# Alimentacao.net
KiCad netlist of a schematic drawn in Altium Designer
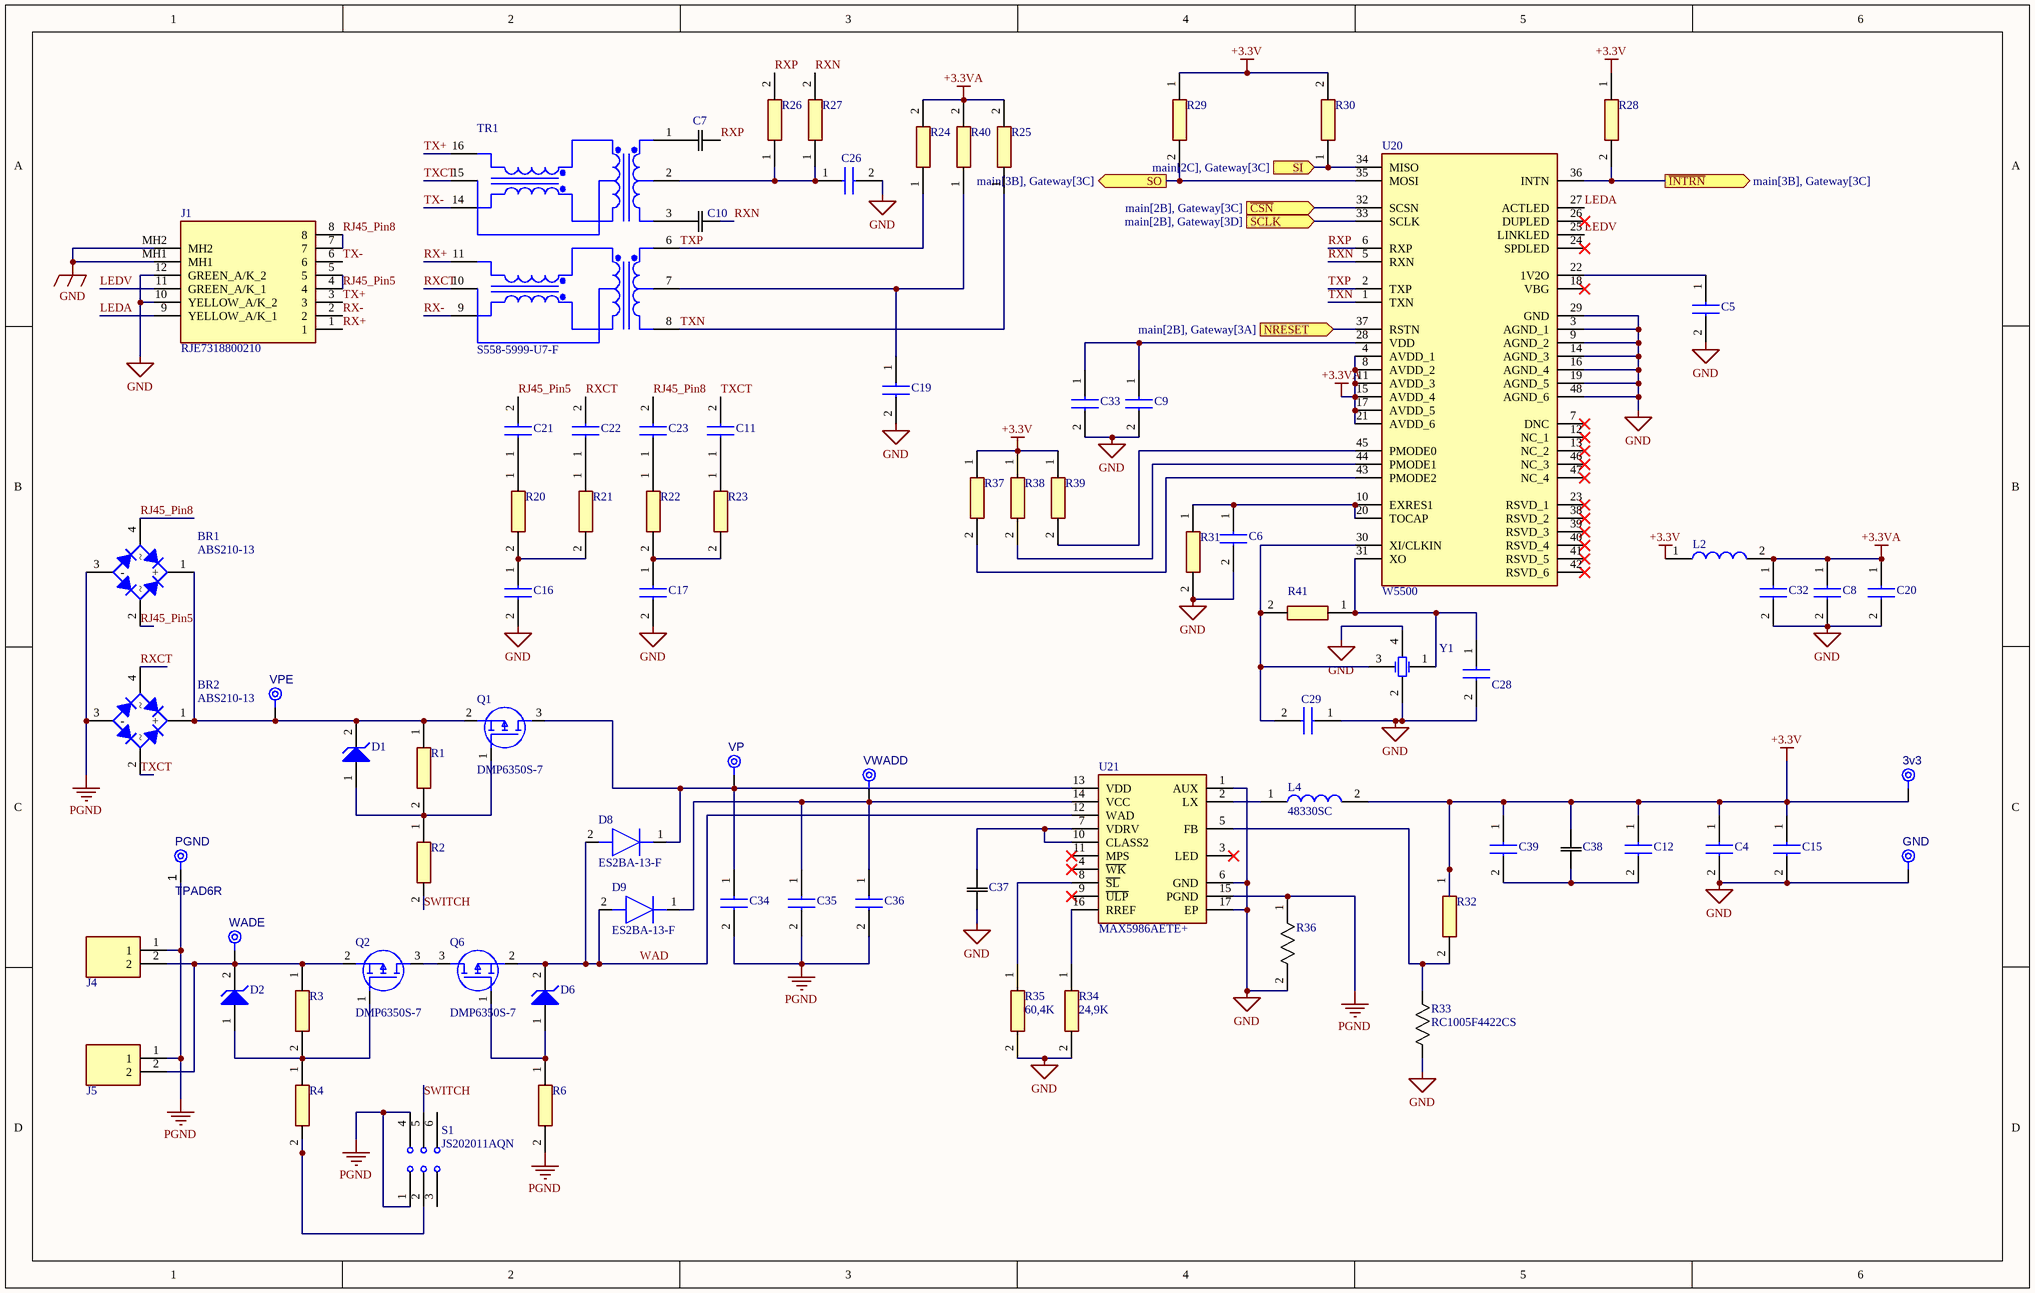
[diagram p0: Alimentacao.SchDoc]

(export (version "E")
  (design (tool "Eeschema 10.0.6"))
  (components
    (comp (ref "3v3")
      (value "TPAD6R")
      (footprint "TP06R")
      (description "0.6mm round")
      (libsource (lib "marina santos") (part "CMP-001-0001-4"))
    )
    (comp (ref "BR1")
      (value "ABS210-13")
      (footprint "SamacSys:ABS21013")
      (description "Bridge Rectifier")
      (fields (field (name "MOUSER PART NUMBER") "621-ABS210-13"))
      (libsource (lib "SamacSys") (part "ABS210-13"))
    )
    (comp (ref "BR2")
      (value "ABS210-13")
      (footprint "SamacSys:ABS21013")
      (description "Bridge Rectifier")
      (fields (field (name "MOUSER PART NUMBER") "621-ABS210-13"))
      (libsource (lib "SamacSys") (part "ABS210-13"))
    )
    (comp (ref "C4")
      (value "C1005X7R1C104KT")
      (footprint "SamacSys:CAPC1005X55N")
      (description "Capacitor")
      (libsource (lib "*") (part "C1005X7R1C104KT"))
    )
    (comp (ref "C5")
      (value "CL05B103KO5NNNC")
      (footprint "SamacSys:CAPC1005X55N")
      (description "Capacitor 10n")
      (libsource (lib "*") (part "CL05B103KO5NNNC"))
    )
    (comp (ref "C6")
      (value "JMK105BC6475MV-F")
      (footprint "SamacSys:CAPC1006X65N")
      (description "Capacitor 4,7u")
      (fields (field (name "MOUSER PART NUMBER") "963-JMK105BC6475MV-F"))
      (libsource (lib "*") (part "JMK105BC6475MV-F"))
    )
    (comp (ref "C7")
      (value "CL05X105KP5NNNC")
      (footprint "CAP_CL05_SAM")
      (description "No Description Available")
      (libsource (lib "CL05X105KP5NNNC") (part "CL05X105KP5NNNC"))
    )
    (comp (ref "C8")
      (value "C1005X7R1C104KT")
      (footprint "SamacSys:CAPC1005X55N")
      (description "Capacitor 100n")
      (libsource (lib "*") (part "C1005X7R1C104KT"))
    )
    (comp (ref "C9")
      (value "C1005X7R1C104KT")
      (footprint "SamacSys:CAPC1005X55N")
      (description "Capacitor 100n")
      (libsource (lib "*") (part "C1005X7R1C104KT"))
    )
    (comp (ref "C10")
      (value "CL05X105KP5NNNC")
      (footprint "CAP_CL05_SAM")
      (description "No Description Available")
      (libsource (lib "CL05X105KP5NNNC") (part "CL05X105KP5NNNC"))
    )
    (comp (ref "C11")
      (value "C1608JB2A223M080AA")
      (footprint "SamacSys:C1608_Commercial")
      (description "Capacitor")
      (fields (field (name "MOUSER PART NUMBER") "810-C1608JB2A223M08A"))
      (libsource (lib "*") (part "C1608JB2A223M080AA"))
    )
    (comp (ref "C12")
      (value "C1005X7R1C104KT")
      (footprint "SamacSys:CAPC1005X55N")
      (description "Capacitor")
      (libsource (lib "*") (part "C1005X7R1C104KT"))
    )
    (comp (ref "C15")
      (value "CL05A106MP8NUB8")
      (footprint "SamacSys:CAPC1005X90N")
      (description "Capacitor 10u")
      (fields (field (name "MOUSER PART NUMBER") "187-CL05A106MP8NUB8"))
      (libsource (lib "*") (part "CL05A106MP8NUB8"))
    )
    (comp (ref "C16")
      (value "CL31B102KJHNNNE")
      (footprint "SamacSys:CAPC3216X180N")
      (description "Capacitor")
      (fields (field (name "MOUSER PART NUMBER") "187-CL31B102KJHNNNE"))
      (libsource (lib "*") (part "CL31B102KJHNNNE"))
    )
    (comp (ref "C17")
      (value "CL31B102KJHNNNE")
      (footprint "SamacSys:CAPC3216X180N")
      (description "Capacitor")
      (fields (field (name "MOUSER PART NUMBER") "187-CL31B102KJHNNNE"))
      (libsource (lib "*") (part "CL31B102KJHNNNE"))
    )
    (comp (ref "C19")
      (value "GRM155R71H223KA12D")
      (footprint "SamacSys:GRM15x")
      (description "Capacitor")
      (fields (field (name "MOUSER PART NUMBER") "81-GRM155R71H223KA12"))
      (libsource (lib "*") (part "GRM155R71H223KA12D"))
    )
    (comp (ref "C20")
      (value "CL05B103KO5NNNC")
      (footprint "SamacSys:CAPC1005X55N")
      (description "Capacitor 10n")
      (libsource (lib "*") (part "CL05B103KO5NNNC"))
    )
    (comp (ref "C21")
      (value "C1608JB2A223M080AA")
      (footprint "SamacSys:C1608_Commercial")
      (description "Capacitor")
      (fields (field (name "MOUSER PART NUMBER") "810-C1608JB2A223M08A"))
      (libsource (lib "*") (part "C1608JB2A223M080AA"))
    )
    (comp (ref "C22")
      (value "C1608JB2A223M080AA")
      (footprint "SamacSys:C1608_Commercial")
      (description "Capacitor")
      (fields (field (name "MOUSER PART NUMBER") "810-C1608JB2A223M08A"))
      (libsource (lib "*") (part "C1608JB2A223M080AA"))
    )
    (comp (ref "C23")
      (value "C1608JB2A223M080AA")
      (footprint "SamacSys:C1608_Commercial")
      (description "Capacitor")
      (fields (field (name "MOUSER PART NUMBER") "810-C1608JB2A223M08A"))
      (libsource (lib "*") (part "C1608JB2A223M080AA"))
    )
    (comp (ref "C26")
      (value "C1005X5R1E104K050BC")
      (footprint "SamacSys:CAPC1005X55N")
      (description "Capacitor")
      (fields (field (name "MOUSER PART NUMBER") "810-C1005X5R1E104K"))
      (libsource (lib "*") (part "C1005X5R1E104K050BC"))
    )
    (comp (ref "C28")
      (value "C1005C0G1H150JT")
      (footprint "SamacSys:CAPC1005X55N")
      (description "Capacitor 15pF")
      (fields (field (name "MANUFACTURER_PART_NUMBER") "CC0402JRNPO9BN150"))
      (libsource (lib "*") (part "CC0402JRNPO9BN150"))
    )
    (comp (ref "C29")
      (value "C1005C0G1H150JT")
      (footprint "SamacSys:CAPC1005X55N")
      (description "Capacitor 15pF")
      (fields (field (name "MANUFACTURER_PART_NUMBER") "CC0402JRNPO9BN150"))
      (libsource (lib "*") (part "CC0402JRNPO9BN150"))
    )
    (comp (ref "C32")
      (value "JMK105BC6475MV-F")
      (footprint "SamacSys:CAPC1006X65N")
      (description "Capacitor 4,7u")
      (fields (field (name "MOUSER PART NUMBER") "963-JMK105BC6475MV-F"))
      (libsource (lib "*") (part "JMK105BC6475MV-F"))
    )
    (comp (ref "C33")
      (value "JMK105BC6475MV-F")
      (footprint "SamacSys:CAPC1006X65N")
      (description "Capacitor 4,7u")
      (fields (field (name "MOUSER PART NUMBER") "963-JMK105BC6475MV-F"))
      (libsource (lib "*") (part "JMK105BC6475MV-F"))
    )
    (comp (ref "C34")
      (value "CC0805KKX7R0BB683")
      (footprint "SamacSys:CAPC2012X145N")
      (description "Capacitor 0,068u")
      (fields (field (name "MOUSER PART NUMBER") "603-CC0805KR0BB683"))
      (libsource (lib "*") (part "CC0805KKX7R0BB683"))
    )
    (comp (ref "C35")
      (value "CL21Y105KCYVPNE")
      (footprint "SamacSys:CAPC2012X145N")
      (description "Capacitor")
      (libsource (lib "SamacSys") (part "CL21Y105KCYVPNE"))
    )
    (comp (ref "C36")
      (value "GRM32ER71J106KA12L")
      (footprint "SamacSys:CAPC3225X270N")
      (description "Capacitor 10u")
      (fields (field (name "MOUSER PART NUMBER") "81-GRM32ER71J106KA2L"))
      (libsource (lib "*") (part "GRM32ER71J106KA12L"))
    )
    (comp (ref "C37")
      (value "CL05X105KP5NNNC")
      (footprint "CAP_CL_05_SAM")
      (description "1u")
      (libsource (lib "CL05X105KP5NNNC") (part "CL05X105KP5NNNC"))
    )
    (comp (ref "C38")
      (value "CL05X105KP5NNNC")
      (footprint "CAP_CL_05_SAM")
      (description "No Description Available")
      (libsource (lib "CL05X105KP5NNNC") (part "CL05X105KP5NNNC"))
    )
    (comp (ref "C39")
      (value "GRM21BR61A476ME15L")
      (footprint "SamacSys:CAPC2012X145N")
      (description "Capacitor")
      (fields (field (name "MOUSER PART NUMBER") "81-GRM21BR61A476ME5L"))
      (libsource (lib "*") (part "GRM21BR61A476ME15L"))
    )
    (comp (ref "D1")
      (value "MMSZ5240B-7-F")
      (footprint "SamacSys:SOD3716X145N")
      (description "D2")
      (fields (field (name "MOUSER PART NUMBER") "621-MMSZ5240B-F"))
      (libsource (lib "SamacSys") (part "MMSZ5240B-7-F"))
    )
    (comp (ref "D2")
      (value "MMSZ5240B-7-F")
      (footprint "SamacSys:SOD3716X145N")
      (description "D2")
      (fields (field (name "MOUSER PART NUMBER") "621-MMSZ5240B-F"))
      (libsource (lib "SamacSys") (part "MMSZ5240B-7-F"))
    )
    (comp (ref "D6")
      (value "MMSZ5240B-7-F")
      (footprint "SamacSys:SOD3716X145N")
      (description "D2")
      (fields (field (name "MOUSER PART NUMBER") "621-MMSZ5240B-F"))
      (libsource (lib "SamacSys") (part "MMSZ5240B-7-F"))
    )
    (comp (ref "D8")
      (value "ES2BA-13-F")
      (footprint "SamacSys:DIOM5226X230N")
      (description "Diode")
      (fields (field (name "MOUSER PART NUMBER") "621-ES2BA-F"))
      (libsource (lib "*") (part "ES2BA-13-F"))
    )
    (comp (ref "D9")
      (value "ES2BA-13-F")
      (footprint "SamacSys:DIOM5226X230N")
      (description "Diode")
      (fields (field (name "MOUSER PART NUMBER") "621-ES2BA-F"))
      (libsource (lib "*") (part "ES2BA-13-F"))
    )
    (comp (ref "GND")
      (value "TPAD6R")
      (footprint "TP06R")
      (description "0.6mm round")
      (libsource (lib "marina santos") (part "CMP-001-0001-4"))
    )
    (comp (ref "J1")
      (value "RJE7318800210")
      (footprint "SamacSys:RJE7318800210")
      (description "Connector")
      (fields (field (name "MOUSER PART NUMBER") "523-RJE7318800210"))
      (libsource (lib "SamacSys") (part "RJE7318800210"))
    )
    (comp (ref "J4")
      (value "OQ0232510000G")
      (footprint "SamacSys:OQ0232510000G")
      (description "Connector")
      (fields (field (name "MOUSER PART NUMBER") "649-220110-D021A01LF"))
      (libsource (lib "*") (part "OQ0232510000G"))
    )
    (comp (ref "J5")
      (value "OQ0232510000G")
      (footprint "SamacSys:OQ0232510000G")
      (description "Connector")
      (fields (field (name "MOUSER PART NUMBER") "649-220110-D021A01LF"))
      (libsource (lib "*") (part "OQ0232510000G"))
    )
    (comp (ref "L2")
      (value "FBMH1608HM101-T")
      (footprint "SamacSys:INDC1608X90N")
      (description "Ferrite Bead")
      (fields (field (name "MOUSER PART NUMBER") "963-FBMH1608HM101-T"))
      (libsource (lib "SamacSys") (part "FBMH1608HM101-T"))
    )
    (comp (ref "L4")
      (value "48330SC")
      (footprint "SamacSys:48101SC")
      (description "Inductor")
      (fields
        (field (name "MANUFACTURER_PART_NUMBER") "48101SC")
        (field (name "MOUSER PART NUMBER") "580-48101SC")
      )
      (libsource (lib "SamacSys") (part "48101SC"))
    )
    (comp (ref "PGND")
      (value "TPAD6R")
      (footprint "TP06R")
      (description "0.6mm round")
      (libsource (lib "") (part "CMP-001-0001-4_1"))
    )
    (comp (ref "Q1")
      (value "DMP6350S-7")
      (footprint "SamacSys:SOT96P240X110-3N")
      (description "MOSFET (P-Channel)")
      (fields (field (name "MOUSER PART NUMBER") "621-DMP6350S-7"))
      (libsource (lib "*") (part "DMP6350S-7"))
    )
    (comp (ref "Q2")
      (value "DMP6350S-7")
      (footprint "SamacSys:SOT96P240X110-3N")
      (description "MOSFET (P-Channel)")
      (fields (field (name "MOUSER PART NUMBER") "621-DMP6350S-7"))
      (libsource (lib "*") (part "DMP6350S-7"))
    )
    (comp (ref "Q6")
      (value "DMP6350S-7")
      (footprint "SamacSys:SOT96P240X110-3N")
      (description "MOSFET (P-Channel)")
      (fields (field (name "MOUSER PART NUMBER") "621-DMP6350S-7"))
      (libsource (lib "*") (part "DMP6350S-7"))
    )
    (comp (ref "R1")
      (value "R0402_1%_100_K__RC0402FR-07100KL_")
      (footprint "SamacSys:RESC1005X40N")
      (description "Resistor 100k")
      (fields (field (name "MANUFACTURER_PART_NUMBER") "R0402 1% 100 K (RC0402FR-07100KL)"))
      (libsource (lib "*") (part "R0402_1%_100_K__RC0402FR-07100KL_"))
    )
    (comp (ref "R2")
      (value "R0402_1%_100_K__RC0402FR-07100KL_")
      (footprint "SamacSys:RESC1005X40N")
      (description "Resistor 100k")
      (fields (field (name "MANUFACTURER_PART_NUMBER") "R0402 1% 100 K (RC0402FR-07100KL)"))
      (libsource (lib "*") (part "R0402_1%_100_K__RC0402FR-07100KL_"))
    )
    (comp (ref "R3")
      (value "R0402_1%_100_K__RC0402FR-07100KL_")
      (footprint "SamacSys:RESC1005X40N")
      (description "Resistor 100k")
      (fields (field (name "MANUFACTURER_PART_NUMBER") "R0402 1% 100 K (RC0402FR-07100KL)"))
      (libsource (lib "*") (part "R0402_1%_100_K__RC0402FR-07100KL_"))
    )
    (comp (ref "R4")
      (value "R0402_1%_100_K__RC0402FR-07100KL_")
      (footprint "SamacSys:RESC1005X40N")
      (description "Resistor 100k")
      (fields (field (name "MANUFACTURER_PART_NUMBER") "R0402 1% 100 K (RC0402FR-07100KL)"))
      (libsource (lib "*") (part "R0402_1%_100_K__RC0402FR-07100KL_"))
    )
    (comp (ref "R6")
      (value "R0402_1%_100_K__RC0402FR-07100KL_")
      (footprint "SamacSys:RESC1005X40N")
      (description "Resistor 100k")
      (fields (field (name "MANUFACTURER_PART_NUMBER") "R0402 1% 100 K (RC0402FR-07100KL)"))
      (libsource (lib "*") (part "R0402_1%_100_K__RC0402FR-07100KL_"))
    )
    (comp (ref "R20")
      (value "RC0603FR-0775RL")
      (footprint "SamacSys:RESC1608X55N")
      (description "Resistor")
      (fields (field (name "MOUSER PART NUMBER") "603-RC0603FR-0775RL"))
      (libsource (lib "*") (part "RC0603FR-0775RL"))
    )
    (comp (ref "R21")
      (value "RC0603FR-0775RL")
      (footprint "SamacSys:RESC1608X55N")
      (description "Resistor")
      (fields (field (name "MOUSER PART NUMBER") "603-RC0603FR-0775RL"))
      (libsource (lib "*") (part "RC0603FR-0775RL"))
    )
    (comp (ref "R22")
      (value "RC0603FR-0775RL")
      (footprint "SamacSys:RESC1608X55N")
      (description "Resistor")
      (fields (field (name "MOUSER PART NUMBER") "603-RC0603FR-0775RL"))
      (libsource (lib "*") (part "RC0603FR-0775RL"))
    )
    (comp (ref "R23")
      (value "RC0603FR-0775RL")
      (footprint "SamacSys:RESC1608X55N")
      (description "Resistor")
      (fields (field (name "MOUSER PART NUMBER") "603-RC0603FR-0775RL"))
      (libsource (lib "*") (part "RC0603FR-0775RL"))
    )
    (comp (ref "R24")
      (value "RC0402FR-0749R9L")
      (footprint "SamacSys:RESC1005X40N")
      (description "Resistor 49,9 ohms")
      (fields (field (name "MOUSER PART NUMBER") "603-RC0402FR-0749R9L"))
      (libsource (lib "*") (part "RC0402FR-0749R9L"))
    )
    (comp (ref "R25")
      (value "RC0402FR-0749R9L")
      (footprint "SamacSys:RESC1005X40N")
      (description "Resistor 49,9 ohms")
      (fields (field (name "MOUSER PART NUMBER") "603-RC0402FR-0749R9L"))
      (libsource (lib "*") (part "RC0402FR-0749R9L"))
    )
    (comp (ref "R26")
      (value "RC0402FR-0782RL")
      (footprint "SamacSys:RESC1005X40N")
      (description "Resistor")
      (fields (field (name "MOUSER PART NUMBER") "603-RC0402FR-0782RL"))
      (libsource (lib "*") (part "RC0402FR-0782RL"))
    )
    (comp (ref "R27")
      (value "RC0402FR-0782RL")
      (footprint "SamacSys:RESC1005X40N")
      (description "Resistor")
      (fields (field (name "MOUSER PART NUMBER") "603-RC0402FR-0782RL"))
      (libsource (lib "*") (part "RC0402FR-0782RL"))
    )
    (comp (ref "R28")
      (value "RC0402FR-074K7L")
      (footprint "SamacSys:RESC1005X40N")
      (description "Resistor 4,7K")
      (fields (field (name "MOUSER PART NUMBER") "603-RC0402FR-074K7L"))
      (libsource (lib "*") (part "RC0402FR-074K7L"))
    )
    (comp (ref "R29")
      (value "RC0402FR-074K7L")
      (footprint "SamacSys:RESC1005X40N")
      (description "Resistor 4,7K")
      (fields (field (name "MOUSER PART NUMBER") "603-RC0402FR-074K7L"))
      (libsource (lib "*") (part "RC0402FR-074K7L"))
    )
    (comp (ref "R30")
      (value "RC0402FR-074K7L")
      (footprint "SamacSys:RESC1005X40N")
      (description "Resistor 4,7 K")
      (fields (field (name "MOUSER PART NUMBER") "603-RC0402FR-074K7L"))
      (libsource (lib "") (part "RC0402FR-074K7L_1"))
    )
    (comp (ref "R31")
      (value "RC0402FR-0712K4L")
      (footprint "SamacSys:RESC1005X40N")
      (description "Resistor 12,4K")
      (fields (field (name "MOUSER PART NUMBER") "603-RC0402FR-0712K4L"))
      (libsource (lib "*") (part "RC0402FR-0712K4L"))
    )
    (comp (ref "R32")
      (value "RC0402FR-0775KL")
      (footprint "SamacSys:RESC1005X40N")
      (description "Resistor")
      (fields (field (name "MOUSER PART NUMBER") "603-RC0402FR-0775KL"))
      (libsource (lib "*") (part "RC0402FR-0775KL"))
    )
    (comp (ref "R33")
      (value "RC1005F4422CS")
      (footprint "RES_1005_SAM-M")
      (description "No Description Available")
      (libsource (lib "RC1005F4422CS") (part "RC1005F4422CS"))
    )
    (comp (ref "R34")
      (value "24,9K")
      (footprint "SamacSys:RESC1005X40N")
      (description "Resistor")
      (fields
        (field (name "MANUFACTURER_PART_NUMBER") "RC0402FR-0724K9L")
        (field (name "MOUSER PART NUMBER") "603-RC0402FR-0724K9L")
      )
      (libsource (lib "*") (part "RC0402FR-0724K9L"))
    )
    (comp (ref "R35")
      (value "60,4K")
      (footprint "SamacSys:RESC1005X40N")
      (description "Resistor 60,4K")
      (fields
        (field (name "MANUFACTURER_PART_NUMBER") "RC0402FR-0760K4L")
        (field (name "MOUSER PART NUMBER") "603-RC0402FR-0760K4L")
      )
      (libsource (lib "*") (part "RC0402FR-0760K4L"))
    )
    (comp (ref "R36")
      (value "RC0805JR-070RL")
      (footprint "SamacSys:CAPC2012X60N")
      (description "Capacitor 0 ohms")
      (fields (field (name "MOUSER PART NUMBER") "603-RC0805JR-070RL"))
      (libsource (lib "SamacSys") (part "RC0805JR-070RL"))
    )
    (comp (ref "R37")
      (value "RC0402FR-0710KL")
      (footprint "SamacSys:RESC1005X40N")
      (description "Resistor 10K")
      (fields (field (name "MOUSER PART NUMBER") "603-RC0402FR-0710KL"))
      (libsource (lib "*") (part "RC0402FR-0710KL"))
    )
    (comp (ref "R38")
      (value "RC0402FR-0710KL")
      (footprint "SamacSys:RESC1005X40N")
      (description "Resistor 10K")
      (fields (field (name "MOUSER PART NUMBER") "603-RC0402FR-0710KL"))
      (libsource (lib "*") (part "RC0402FR-0710KL"))
    )
    (comp (ref "R39")
      (value "RC0402FR-0710KL")
      (footprint "SamacSys:RESC1005X40N")
      (description "Resistor 10K")
      (fields (field (name "MOUSER PART NUMBER") "603-RC0402FR-0710KL"))
      (libsource (lib "*") (part "RC0402FR-0710KL"))
    )
    (comp (ref "R40")
      (value "RC0402FR-0710RL")
      (footprint "SamacSys:RESC1005X40N")
      (description "Resistor 10 ohms")
      (fields (field (name "MOUSER PART NUMBER") "603-RC0402FR-0710RL"))
      (libsource (lib "*") (part "RC0402FR-0710RL"))
    )
    (comp (ref "R41")
      (value "RC0402FR-071ML")
      (footprint "SamacSys:RESC1005X40N")
      (description "Resistor 1M")
      (fields (field (name "MOUSER PART NUMBER") "603-RC0402FR-071ML"))
      (libsource (lib "*") (part "RC0402FR-071ML"))
    )
    (comp (ref "S1")
      (value "JS202011AQN")
      (footprint "SamacSys:JS202011AQN")
      (description "Switch")
      (fields (field (name "MOUSER PART NUMBER") "611-JS202011AQN"))
      (libsource (lib "SamacSys") (part "JS202011AQN"))
    )
    (comp (ref "TR1")
      (value "S558-5999-U7-F")
      (footprint "SamacSys:SOIC127P920X571-16N")
      (description "Integrated Circuit")
      (fields (field (name "MOUSER PART NUMBER") "530-S558-5999-U7-F"))
      (libsource (lib "SamacSys") (part "S558-5999-U7-F"))
    )
    (comp (ref "U20")
      (value "W5500")
      (footprint "SamacSys:QFP50P900X900X160-48N")
      (description "Integrated Circuit")
      (fields (field (name "MOUSER PART NUMBER") "950-W5500"))
      (libsource (lib "SamacSys") (part "W5500"))
    )
    (comp (ref "U21")
      (value "MAX5986AETE+")
      (footprint "SamacSys:QFN80P500X500X80-17N")
      (description "Integrated Circuit")
      (fields (field (name "MOUSER PART NUMBER") "700-MAX5986AETE+"))
      (libsource (lib "SamacSys") (part "MAX5986AETE+"))
    )
    (comp (ref "VP")
      (value "TPAD6R")
      (footprint "TP06R")
      (description "0.6mm round")
      (libsource (lib "marina santos") (part "CMP-001-0001-4"))
    )
    (comp (ref "VPE")
      (value "TPAD6R")
      (footprint "TP06R")
      (description "0.6mm round")
      (libsource (lib "marina santos") (part "CMP-001-0001-4"))
    )
    (comp (ref "VWADD")
      (value "TPAD6R")
      (footprint "TP06R")
      (description "0.6mm round")
      (libsource (lib "marina santos") (part "CMP-001-0001-4"))
    )
    (comp (ref "WADE")
      (value "TPAD6R")
      (footprint "TP06R")
      (description "0.6mm round")
      (libsource (lib "marina santos") (part "CMP-001-0001-4"))
    )
    (comp (ref "Y1")
      (value "RH100-25.000-12-F-1010-TR")
      (footprint "SamacSys:RH1002500012F1010TR")
      (description "Crystal or Oscillator")
      (libsource (lib "SamacSys") (part "RH100-25.000-12-F-1010-TR"))
    )
  )
  (nets
    (net (code "1") (name "+3.3V") (class "Default")
      (node (ref "3v3") (pin "1") (pinfunction "TP_1") (pintype "passive"))
      (node (ref "C12") (pin "1") (pinfunction "1_1") (pintype "passive"))
      (node (ref "C15") (pin "1") (pinfunction "1_1") (pintype "passive"))
      (node (ref "C38") (pin "2") (pinfunction "2_2") (pintype "passive"))
      (node (ref "C39") (pin "1") (pinfunction "1_1") (pintype "passive"))
      (node (ref "C4") (pin "1") (pinfunction "1_1") (pintype "passive"))
      (node (ref "L2") (pin "1") (pinfunction "1_1") (pintype "passive"))
      (node (ref "L4") (pin "2") (pinfunction "2_2") (pintype "passive"))
      (node (ref "R28") (pin "1") (pinfunction "1_1") (pintype "passive"))
      (node (ref "R29") (pin "1") (pinfunction "1_1") (pintype "passive"))
      (node (ref "R30") (pin "2") (pinfunction "2_2") (pintype "passive"))
      (node (ref "R32") (pin "1") (pinfunction "1_1") (pintype "passive"))
      (node (ref "R37") (pin "1") (pinfunction "1_1") (pintype "passive"))
      (node (ref "R38") (pin "1") (pinfunction "1_1") (pintype "passive"))
      (node (ref "R39") (pin "1") (pinfunction "1_1") (pintype "passive"))
    )
    (net (code "2") (name "+3.3VA") (class "Default")
      (node (ref "C20") (pin "1") (pinfunction "1_1") (pintype "passive"))
      (node (ref "C32") (pin "1") (pinfunction "1_1") (pintype "passive"))
      (node (ref "C8") (pin "1") (pinfunction "1_1") (pintype "passive"))
      (node (ref "L2") (pin "2") (pinfunction "2_2") (pintype "passive"))
      (node (ref "R24") (pin "2") (pinfunction "2_2") (pintype "passive"))
      (node (ref "R25") (pin "2") (pinfunction "2_2") (pintype "passive"))
      (node (ref "R40") (pin "2") (pinfunction "2_2") (pintype "passive"))
      (node (ref "U20") (pin "11") (pinfunction "AVDD_3_11") (pintype "passive"))
      (node (ref "U20") (pin "15") (pinfunction "AVDD_4_15") (pintype "passive"))
      (node (ref "U20") (pin "17") (pinfunction "AVDD_5_17") (pintype "passive"))
      (node (ref "U20") (pin "21") (pinfunction "AVDD_6_21") (pintype "passive"))
      (node (ref "U20") (pin "4") (pinfunction "AVDD_1_4") (pintype "passive"))
      (node (ref "U20") (pin "8") (pinfunction "AVDD_2_8") (pintype "passive"))
    )
    (net (code "3") (name "/LEDA") (class "Default")
      (node (ref "J1") (pin "9") (pinfunction "YELLOW_A/K_1_9") (pintype "passive"))
      (node (ref "U20") (pin "27") (pinfunction "ACTLED_27") (pintype "passive"))
    )
    (net (code "4") (name "/LEDV") (class "Default")
      (node (ref "J1") (pin "11") (pinfunction "GREEN_A/K_1_11") (pintype "passive"))
      (node (ref "U20") (pin "25") (pinfunction "LINKLED_25") (pintype "passive"))
    )
    (net (code "5") (name "/NRESET") (class "Default")
      (node (ref "U20") (pin "37") (pinfunction "RSTN_37") (pintype "passive"))
    )
    (net (code "6") (name "/RJ45_Pin5") (class "Default")
      (node (ref "BR1") (pin "2") (pinfunction "~_2") (pintype "passive"))
      (node (ref "C21") (pin "2") (pinfunction "2_2") (pintype "passive"))
      (node (ref "J1") (pin "4") (pinfunction "4_4") (pintype "passive"))
      (node (ref "J1") (pin "5") (pinfunction "5_5") (pintype "passive"))
    )
    (net (code "7") (name "/RJ45_Pin8") (class "Default")
      (node (ref "BR1") (pin "4") (pinfunction "~_4") (pintype "passive"))
      (node (ref "C23") (pin "2") (pinfunction "2_2") (pintype "passive"))
      (node (ref "J1") (pin "7") (pinfunction "7_7") (pintype "passive"))
      (node (ref "J1") (pin "8") (pinfunction "8_8") (pintype "passive"))
    )
    (net (code "8") (name "/RX+") (class "Default")
      (node (ref "J1") (pin "1") (pinfunction "1_1") (pintype "passive"))
      (node (ref "TR1") (pin "11") (pinfunction "RX+_11") (pintype "passive"))
    )
    (net (code "9") (name "/RX-") (class "Default")
      (node (ref "J1") (pin "2") (pinfunction "2_2") (pintype "passive"))
      (node (ref "TR1") (pin "9") (pinfunction "RX-_9") (pintype "passive"))
    )
    (net (code "10") (name "/RXCT") (class "Default")
      (node (ref "BR2") (pin "4") (pinfunction "~_4") (pintype "passive"))
      (node (ref "C22") (pin "2") (pinfunction "2_2") (pintype "passive"))
      (node (ref "TR1") (pin "10") (pinfunction "RXCT_10") (pintype "passive"))
    )
    (net (code "11") (name "/RXN") (class "Default")
      (node (ref "C10") (pin "2") (pinfunction "2_2") (pintype "passive"))
      (node (ref "R27") (pin "2") (pinfunction "2_2") (pintype "passive"))
      (node (ref "U20") (pin "5") (pinfunction "RXN_5") (pintype "passive"))
    )
    (net (code "12") (name "/RXP") (class "Default")
      (node (ref "C7") (pin "2") (pinfunction "2_2") (pintype "passive"))
      (node (ref "R26") (pin "2") (pinfunction "2_2") (pintype "passive"))
      (node (ref "U20") (pin "6") (pinfunction "RXP_6") (pintype "passive"))
    )
    (net (code "13") (name "/SCLK") (class "Default")
      (node (ref "U20") (pin "33") (pinfunction "SCLK_33") (pintype "passive"))
    )
    (net (code "14") (name "/SI") (class "Default")
      (node (ref "R30") (pin "1") (pinfunction "1_1") (pintype "passive"))
      (node (ref "U20") (pin "34") (pinfunction "MISO_34") (pintype "passive"))
    )
    (net (code "15") (name "/SO") (class "Default")
      (node (ref "R29") (pin "2") (pinfunction "2_2") (pintype "passive"))
      (node (ref "U20") (pin "35") (pinfunction "MOSI_35") (pintype "passive"))
    )
    (net (code "16") (name "/SWITCH") (class "Default")
      (node (ref "R2") (pin "2") (pinfunction "2_2") (pintype "passive"))
      (node (ref "S1") (pin "5") (pinfunction "C_2_5") (pintype "passive"))
    )
    (net (code "17") (name "/TX+") (class "Default")
      (node (ref "J1") (pin "3") (pinfunction "3_3") (pintype "passive"))
      (node (ref "TR1") (pin "16") (pinfunction "TX+_16") (pintype "passive"))
    )
    (net (code "18") (name "/TX-") (class "Default")
      (node (ref "J1") (pin "6") (pinfunction "6_6") (pintype "passive"))
      (node (ref "TR1") (pin "14") (pinfunction "TX-_14") (pintype "passive"))
    )
    (net (code "19") (name "/TXCT") (class "Default")
      (node (ref "BR2") (pin "2") (pinfunction "~_2") (pintype "passive"))
      (node (ref "C11") (pin "2") (pinfunction "2_2") (pintype "passive"))
      (node (ref "TR1") (pin "15") (pinfunction "TXCT_15") (pintype "passive"))
    )
    (net (code "20") (name "/TXN") (class "Default")
      (node (ref "R25") (pin "1") (pinfunction "1_1") (pintype "passive"))
      (node (ref "TR1") (pin "8") (pinfunction "RD-_8") (pintype "passive"))
      (node (ref "U20") (pin "1") (pinfunction "TXN_1") (pintype "passive"))
    )
    (net (code "21") (name "/TXP") (class "Default")
      (node (ref "R24") (pin "1") (pinfunction "1_1") (pintype "passive"))
      (node (ref "TR1") (pin "6") (pinfunction "RD+_6") (pintype "passive"))
      (node (ref "U20") (pin "2") (pinfunction "TXP_2") (pintype "passive"))
    )
    (net (code "22") (name "/WAD") (class "Default")
      (node (ref "D6") (pin "2") (pinfunction "A_2") (pintype "passive"))
      (node (ref "D8") (pin "2") (pinfunction "A_2") (pintype "passive"))
      (node (ref "D9") (pin "2") (pinfunction "A_2") (pintype "passive"))
      (node (ref "Q6") (pin "2") (pinfunction "S_2") (pintype "passive"))
      (node (ref "U21") (pin "12") (pinfunction "WAD_12") (pintype "passive"))
    )
    (net (code "23") (name "/~{CSN}") (class "Default")
      (node (ref "U20") (pin "32") (pinfunction "SCSN_32") (pintype "passive"))
    )
    (net (code "24") (name "/~{INTRN}") (class "Default")
      (node (ref "R28") (pin "2") (pinfunction "2_2") (pintype "passive"))
      (node (ref "U20") (pin "36") (pinfunction "INTN_36") (pintype "passive"))
    )
    (net (code "25") (name "GND") (class "Default")
      (node (ref "C15") (pin "2") (pinfunction "2_2") (pintype "passive"))
      (node (ref "C16") (pin "2") (pinfunction "2_2") (pintype "passive"))
      (node (ref "C17") (pin "2") (pinfunction "2_2") (pintype "passive"))
      (node (ref "C19") (pin "2") (pinfunction "2_2") (pintype "passive"))
      (node (ref "C20") (pin "2") (pinfunction "2_2") (pintype "passive"))
      (node (ref "C26") (pin "2") (pinfunction "2_2") (pintype "passive"))
      (node (ref "C28") (pin "2") (pinfunction "2_2") (pintype "passive"))
      (node (ref "C29") (pin "1") (pinfunction "1_1") (pintype "passive"))
      (node (ref "C32") (pin "2") (pinfunction "2_2") (pintype "passive"))
      (node (ref "C33") (pin "2") (pinfunction "2_2") (pintype "passive"))
      (node (ref "C37") (pin "1") (pinfunction "1_1") (pintype "passive"))
      (node (ref "C4") (pin "2") (pinfunction "2_2") (pintype "passive"))
      (node (ref "C5") (pin "2") (pinfunction "2_2") (pintype "passive"))
      (node (ref "C6") (pin "2") (pinfunction "2_2") (pintype "passive"))
      (node (ref "C8") (pin "2") (pinfunction "2_2") (pintype "passive"))
      (node (ref "C9") (pin "2") (pinfunction "2_2") (pintype "passive"))
      (node (ref "GND") (pin "1") (pinfunction "TP_1") (pintype "passive"))
      (node (ref "J1") (pin "10") (pinfunction "YELLOW_A/K_2_10") (pintype "passive"))
      (node (ref "J1") (pin "12") (pinfunction "GREEN_A/K_2_12") (pintype "passive"))
      (node (ref "J1") (pin "MH1") (pinfunction "MH1_MH1") (pintype "passive"))
      (node (ref "J1") (pin "MH2") (pinfunction "MH2_MH2") (pintype "passive"))
      (node (ref "R31") (pin "2") (pinfunction "2_2") (pintype "passive"))
      (node (ref "R33") (pin "1") (pinfunction "1_1") (pintype "passive"))
      (node (ref "R34") (pin "2") (pinfunction "2_2") (pintype "passive"))
      (node (ref "R35") (pin "2") (pinfunction "2_2") (pintype "passive"))
      (node (ref "R36") (pin "2") (pinfunction "2_2") (pintype "passive"))
      (node (ref "U20") (pin "14") (pinfunction "AGND_3_14") (pintype "passive"))
      (node (ref "U20") (pin "16") (pinfunction "AGND_4_16") (pintype "passive"))
      (node (ref "U20") (pin "19") (pinfunction "AGND_5_19") (pintype "passive"))
      (node (ref "U20") (pin "29") (pinfunction "GND_29") (pintype "passive"))
      (node (ref "U20") (pin "3") (pinfunction "AGND_1_3") (pintype "passive"))
      (node (ref "U20") (pin "48") (pinfunction "AGND_6_48") (pintype "passive"))
      (node (ref "U20") (pin "9") (pinfunction "AGND_2_9") (pintype "passive"))
      (node (ref "U21") (pin "1") (pinfunction "AUX_1") (pintype "passive"))
      (node (ref "U21") (pin "17") (pinfunction "EP_17") (pintype "passive"))
      (node (ref "U21") (pin "6") (pinfunction "GND_6") (pintype "passive"))
      (node (ref "Y1") (pin "2") (pinfunction "NC_1_2") (pintype "passive"))
      (node (ref "Y1") (pin "4") (pinfunction "NC_2_4") (pintype "passive"))
    )
    (net (code "26") (name "Net-(BR1-+)") (class "Default")
      (node (ref "BR1") (pin "1") (pinfunction "+_1") (pintype "passive"))
      (node (ref "BR2") (pin "1") (pinfunction "+_1") (pintype "passive"))
      (node (ref "D1") (pin "2") (pinfunction "A_2") (pintype "passive"))
      (node (ref "Q1") (pin "2") (pinfunction "S_2") (pintype "passive"))
      (node (ref "R1") (pin "1") (pinfunction "1_1") (pintype "passive"))
      (node (ref "VPE") (pin "1") (pinfunction "TP_1") (pintype "passive"))
    )
    (net (code "27") (name "Net-(C11-Pad1)") (class "Default")
      (node (ref "C11") (pin "1") (pinfunction "1_1") (pintype "passive"))
      (node (ref "R23") (pin "1") (pinfunction "1_1") (pintype "passive"))
    )
    (net (code "28") (name "Net-(C12-Pad2)") (class "Default")
      (node (ref "C12") (pin "2") (pinfunction "2_2") (pintype "passive"))
      (node (ref "C38") (pin "1") (pinfunction "1_1") (pintype "passive"))
      (node (ref "C39") (pin "2") (pinfunction "2_2") (pintype "passive"))
    )
    (net (code "29") (name "Net-(C16-Pad1)") (class "Default")
      (node (ref "C16") (pin "1") (pinfunction "1_1") (pintype "passive"))
      (node (ref "R20") (pin "2") (pinfunction "2_2") (pintype "passive"))
      (node (ref "R21") (pin "2") (pinfunction "2_2") (pintype "passive"))
    )
    (net (code "30") (name "Net-(C17-Pad1)") (class "Default")
      (node (ref "C17") (pin "1") (pinfunction "1_1") (pintype "passive"))
      (node (ref "R22") (pin "2") (pinfunction "2_2") (pintype "passive"))
      (node (ref "R23") (pin "2") (pinfunction "2_2") (pintype "passive"))
    )
    (net (code "31") (name "Net-(C21-Pad1)") (class "Default")
      (node (ref "C21") (pin "1") (pinfunction "1_1") (pintype "passive"))
      (node (ref "R20") (pin "1") (pinfunction "1_1") (pintype "passive"))
    )
    (net (code "32") (name "Net-(C22-Pad1)") (class "Default")
      (node (ref "C22") (pin "1") (pinfunction "1_1") (pintype "passive"))
      (node (ref "R21") (pin "1") (pinfunction "1_1") (pintype "passive"))
    )
    (net (code "33") (name "Net-(C23-Pad1)") (class "Default")
      (node (ref "C23") (pin "1") (pinfunction "1_1") (pintype "passive"))
      (node (ref "R22") (pin "1") (pinfunction "1_1") (pintype "passive"))
    )
    (net (code "34") (name "Net-(D1-K)") (class "Default")
      (node (ref "D1") (pin "1") (pinfunction "K_1") (pintype "passive"))
      (node (ref "Q1") (pin "1") (pinfunction "G_1") (pintype "passive"))
      (node (ref "R1") (pin "2") (pinfunction "2_2") (pintype "passive"))
      (node (ref "R2") (pin "1") (pinfunction "1_1") (pintype "passive"))
    )
    (net (code "35") (name "Net-(D2-A)") (class "Default")
      (node (ref "D2") (pin "2") (pinfunction "A_2") (pintype "passive"))
      (node (ref "J4") (pin "2") (pinfunction "2_2") (pintype "passive"))
      (node (ref "J5") (pin "2") (pinfunction "2_2") (pintype "passive"))
      (node (ref "Q2") (pin "2") (pinfunction "S_2") (pintype "passive"))
      (node (ref "R3") (pin "1") (pinfunction "1_1") (pintype "passive"))
      (node (ref "WADE") (pin "1") (pinfunction "TP_1") (pintype "passive"))
    )
    (net (code "36") (name "Net-(D2-K)") (class "Default")
      (node (ref "D2") (pin "1") (pinfunction "K_1") (pintype "passive"))
      (node (ref "Q2") (pin "1") (pinfunction "G_1") (pintype "passive"))
      (node (ref "R3") (pin "2") (pinfunction "2_2") (pintype "passive"))
      (node (ref "R4") (pin "1") (pinfunction "1_1") (pintype "passive"))
    )
    (net (code "37") (name "Net-(D6-K)") (class "Default")
      (node (ref "D6") (pin "1") (pinfunction "K_1") (pintype "passive"))
      (node (ref "Q6") (pin "1") (pinfunction "G_1") (pintype "passive"))
      (node (ref "R6") (pin "1") (pinfunction "1_1") (pintype "passive"))
    )
    (net (code "38") (name "Net-(D8-K)") (class "Default")
      (node (ref "C34") (pin "1") (pinfunction "1_1") (pintype "passive"))
      (node (ref "D8") (pin "1") (pinfunction "K_1") (pintype "passive"))
      (node (ref "Q1") (pin "3") (pinfunction "D_3") (pintype "passive"))
      (node (ref "U21") (pin "13") (pinfunction "VDD_13") (pintype "passive"))
      (node (ref "VP") (pin "1") (pinfunction "TP_1") (pintype "passive"))
    )
    (net (code "39") (name "Net-(D9-K)") (class "Default")
      (node (ref "C35") (pin "1") (pinfunction "1_1") (pintype "passive"))
      (node (ref "C36") (pin "1") (pinfunction "1_1") (pintype "passive"))
      (node (ref "D9") (pin "1") (pinfunction "K_1") (pintype "passive"))
      (node (ref "U21") (pin "14") (pinfunction "VCC_14") (pintype "passive"))
      (node (ref "VWADD") (pin "1") (pinfunction "TP_1") (pintype "passive"))
    )
    (net (code "40") (name "Net-(Q2-D)") (class "Default")
      (node (ref "Q2") (pin "3") (pinfunction "D_3") (pintype "passive"))
      (node (ref "Q6") (pin "3") (pinfunction "D_3") (pintype "passive"))
    )
    (net (code "41") (name "Net-(S1-C_1)") (class "Default")
      (node (ref "R4") (pin "2") (pinfunction "2_2") (pintype "passive"))
      (node (ref "S1") (pin "2") (pinfunction "C_1_2") (pintype "passive"))
    )
    (net (code "42") (name "Net-(TR1-RDCT)") (class "Default")
      (node (ref "C19") (pin "1") (pinfunction "1_1") (pintype "passive"))
      (node (ref "R40") (pin "1") (pinfunction "1_1") (pintype "passive"))
      (node (ref "TR1") (pin "7") (pinfunction "RDCT_7") (pintype "passive"))
    )
    (net (code "43") (name "Net-(TR1-TD+)") (class "Default")
      (node (ref "C7") (pin "1") (pinfunction "1_1") (pintype "passive"))
      (node (ref "TR1") (pin "1") (pinfunction "TD+_1") (pintype "passive"))
    )
    (net (code "44") (name "Net-(TR1-TD-)") (class "Default")
      (node (ref "C10") (pin "1") (pinfunction "1_1") (pintype "passive"))
      (node (ref "TR1") (pin "3") (pinfunction "TD-_3") (pintype "passive"))
    )
    (net (code "45") (name "Net-(TR1-TDCT)") (class "Default")
      (node (ref "C26") (pin "1") (pinfunction "1_1") (pintype "passive"))
      (node (ref "R26") (pin "1") (pinfunction "1_1") (pintype "passive"))
      (node (ref "R27") (pin "1") (pinfunction "1_1") (pintype "passive"))
      (node (ref "TR1") (pin "2") (pinfunction "TDCT_2") (pintype "passive"))
    )
    (net (code "46") (name "Net-(U20-1V2O)") (class "Default")
      (node (ref "C5") (pin "1") (pinfunction "1_1") (pintype "passive"))
      (node (ref "U20") (pin "22") (pinfunction "1V2O_22") (pintype "passive"))
    )
    (net (code "47") (name "Net-(U20-EXRES1)") (class "Default")
      (node (ref "C6") (pin "1") (pinfunction "1_1") (pintype "passive"))
      (node (ref "R31") (pin "1") (pinfunction "1_1") (pintype "passive"))
      (node (ref "U20") (pin "10") (pinfunction "EXRES1_10") (pintype "passive"))
      (node (ref "U20") (pin "20") (pinfunction "TOCAP_20") (pintype "passive"))
    )
    (net (code "48") (name "Net-(U20-PMODE0)") (class "Default")
      (node (ref "R39") (pin "2") (pinfunction "2_2") (pintype "passive"))
      (node (ref "U20") (pin "45") (pinfunction "PMODE0_45") (pintype "passive"))
    )
    (net (code "49") (name "Net-(U20-PMODE1)") (class "Default")
      (node (ref "R38") (pin "2") (pinfunction "2_2") (pintype "passive"))
      (node (ref "U20") (pin "44") (pinfunction "PMODE1_44") (pintype "passive"))
    )
    (net (code "50") (name "Net-(U20-PMODE2)") (class "Default")
      (node (ref "R37") (pin "2") (pinfunction "2_2") (pintype "passive"))
      (node (ref "U20") (pin "43") (pinfunction "PMODE2_43") (pintype "passive"))
    )
    (net (code "51") (name "Net-(U20-VDD)") (class "Default")
      (node (ref "C33") (pin "1") (pinfunction "1_1") (pintype "passive"))
      (node (ref "C9") (pin "1") (pinfunction "1_1") (pintype "passive"))
      (node (ref "U20") (pin "28") (pinfunction "VDD_28") (pintype "passive"))
    )
    (net (code "52") (name "Net-(U20-XI{slash}CLKIN)") (class "Default")
      (node (ref "C29") (pin "2") (pinfunction "2_2") (pintype "passive"))
      (node (ref "R41") (pin "2") (pinfunction "2_2") (pintype "passive"))
      (node (ref "U20") (pin "30") (pinfunction "XI/CLKIN_30") (pintype "passive"))
      (node (ref "Y1") (pin "3") (pinfunction "CRYSTAL_2_3") (pintype "passive"))
    )
    (net (code "53") (name "Net-(U20-XO)") (class "Default")
      (node (ref "C28") (pin "1") (pinfunction "1_1") (pintype "passive"))
      (node (ref "R41") (pin "1") (pinfunction "1_1") (pintype "passive"))
      (node (ref "U20") (pin "31") (pinfunction "XO_31") (pintype "passive"))
      (node (ref "Y1") (pin "1") (pinfunction "CRYSTAL_1_1") (pintype "passive"))
    )
    (net (code "54") (name "Net-(U21-CLASS2)") (class "Default")
      (node (ref "C37") (pin "2") (pinfunction "2_2") (pintype "passive"))
      (node (ref "U21") (pin "10") (pinfunction "CLASS2_10") (pintype "passive"))
      (node (ref "U21") (pin "7") (pinfunction "VDRV_7") (pintype "passive"))
    )
    (net (code "55") (name "Net-(U21-FB)") (class "Default")
      (node (ref "R32") (pin "2") (pinfunction "2_2") (pintype "passive"))
      (node (ref "R33") (pin "2") (pinfunction "2_2") (pintype "passive"))
      (node (ref "U21") (pin "5") (pinfunction "FB_5") (pintype "passive"))
    )
    (net (code "56") (name "Net-(U21-LX)") (class "Default")
      (node (ref "L4") (pin "1") (pinfunction "1_1") (pintype "passive"))
      (node (ref "U21") (pin "2") (pinfunction "LX_2") (pintype "passive"))
    )
    (net (code "57") (name "Net-(U21-RREF)") (class "Default")
      (node (ref "R34") (pin "1") (pinfunction "1_1") (pintype "passive"))
      (node (ref "U21") (pin "16") (pinfunction "RREF_16") (pintype "passive"))
    )
    (net (code "58") (name "Net-(U21-~{SL})") (class "Default")
      (node (ref "R35") (pin "1") (pinfunction "1_1") (pintype "passive"))
      (node (ref "U21") (pin "8") (pinfunction "~{SL}_8") (pintype "passive"))
    )
    (net (code "59") (name "PGND") (class "Default")
      (node (ref "BR1") (pin "3") (pinfunction "-_3") (pintype "passive"))
      (node (ref "BR2") (pin "3") (pinfunction "-_3") (pintype "passive"))
      (node (ref "C34") (pin "2") (pinfunction "2_2") (pintype "passive"))
      (node (ref "C35") (pin "2") (pinfunction "2_2") (pintype "passive"))
      (node (ref "C36") (pin "2") (pinfunction "2_2") (pintype "passive"))
      (node (ref "J4") (pin "1") (pinfunction "1_1") (pintype "passive"))
      (node (ref "J5") (pin "1") (pinfunction "1_1") (pintype "passive"))
      (node (ref "PGND") (pin "1") (pinfunction "TP_1") (pintype "passive"))
      (node (ref "R36") (pin "1") (pinfunction "1_1") (pintype "passive"))
      (node (ref "R6") (pin "2") (pinfunction "2_2") (pintype "passive"))
      (node (ref "S1") (pin "1") (pinfunction "NC_1_1") (pintype "passive"))
      (node (ref "S1") (pin "4") (pinfunction "NC_2_4") (pintype "passive"))
      (node (ref "U21") (pin "15") (pinfunction "PGND_15") (pintype "passive"))
    )
    (net (code "60") (name "unconnected-(S1-NO_1-Pad3)") (class "Default")
      (node (ref "S1") (pin "3") (pinfunction "NO_1_3") (pintype "passive"))
    )
    (net (code "61") (name "unconnected-(S1-NO_2-Pad6)") (class "Default")
      (node (ref "S1") (pin "6") (pinfunction "NO_2_6") (pintype "passive"))
    )
    (net (code "62") (name "unconnected-(U20-DNC-Pad7)") (class "Default")
      (node (ref "U20") (pin "7") (pinfunction "DNC_7") (pintype "passive+no_connect"))
    )
    (net (code "63") (name "unconnected-(U20-DUPLED-Pad26)") (class "Default")
      (node (ref "U20") (pin "26") (pinfunction "DUPLED_26") (pintype "passive+no_connect"))
    )
    (net (code "64") (name "unconnected-(U20-NC_1-Pad12)") (class "Default")
      (node (ref "U20") (pin "12") (pinfunction "NC_1_12") (pintype "passive+no_connect"))
    )
    (net (code "65") (name "unconnected-(U20-NC_2-Pad13)") (class "Default")
      (node (ref "U20") (pin "13") (pinfunction "NC_2_13") (pintype "passive+no_connect"))
    )
    (net (code "66") (name "unconnected-(U20-NC_3-Pad46)") (class "Default")
      (node (ref "U20") (pin "46") (pinfunction "NC_3_46") (pintype "passive+no_connect"))
    )
    (net (code "67") (name "unconnected-(U20-NC_4-Pad47)") (class "Default")
      (node (ref "U20") (pin "47") (pinfunction "NC_4_47") (pintype "passive+no_connect"))
    )
    (net (code "68") (name "unconnected-(U20-RSVD_1-Pad23)") (class "Default")
      (node (ref "U20") (pin "23") (pinfunction "RSVD_1_23") (pintype "passive+no_connect"))
    )
    (net (code "69") (name "unconnected-(U20-RSVD_2-Pad38)") (class "Default")
      (node (ref "U20") (pin "38") (pinfunction "RSVD_2_38") (pintype "passive+no_connect"))
    )
    (net (code "70") (name "unconnected-(U20-RSVD_3-Pad39)") (class "Default")
      (node (ref "U20") (pin "39") (pinfunction "RSVD_3_39") (pintype "passive+no_connect"))
    )
    (net (code "71") (name "unconnected-(U20-RSVD_4-Pad40)") (class "Default")
      (node (ref "U20") (pin "40") (pinfunction "RSVD_4_40") (pintype "passive+no_connect"))
    )
    (net (code "72") (name "unconnected-(U20-RSVD_5-Pad41)") (class "Default")
      (node (ref "U20") (pin "41") (pinfunction "RSVD_5_41") (pintype "passive+no_connect"))
    )
    (net (code "73") (name "unconnected-(U20-RSVD_6-Pad42)") (class "Default")
      (node (ref "U20") (pin "42") (pinfunction "RSVD_6_42") (pintype "passive+no_connect"))
    )
    (net (code "74") (name "unconnected-(U20-SPDLED-Pad24)") (class "Default")
      (node (ref "U20") (pin "24") (pinfunction "SPDLED_24") (pintype "passive+no_connect"))
    )
    (net (code "75") (name "unconnected-(U20-VBG-Pad18)") (class "Default")
      (node (ref "U20") (pin "18") (pinfunction "VBG_18") (pintype "passive+no_connect"))
    )
    (net (code "76") (name "unconnected-(U21-LED-Pad3)") (class "Default")
      (node (ref "U21") (pin "3") (pinfunction "LED_3") (pintype "passive+no_connect"))
    )
    (net (code "77") (name "unconnected-(U21-MPS-Pad11)") (class "Default")
      (node (ref "U21") (pin "11") (pinfunction "MPS_11") (pintype "passive+no_connect"))
    )
    (net (code "78") (name "unconnected-(U21-~{ULP}-Pad9)") (class "Default")
      (node (ref "U21") (pin "9") (pinfunction "~{ULP}_9") (pintype "passive+no_connect"))
    )
    (net (code "79") (name "unconnected-(U21-~{WK}-Pad4)") (class "Default")
      (node (ref "U21") (pin "4") (pinfunction "~{WK}_4") (pintype "passive+no_connect"))
    )
  )
)
